# NMEA0183Breakout-2_0.net
KiCad netlist of a schematic drawn in EAGLE
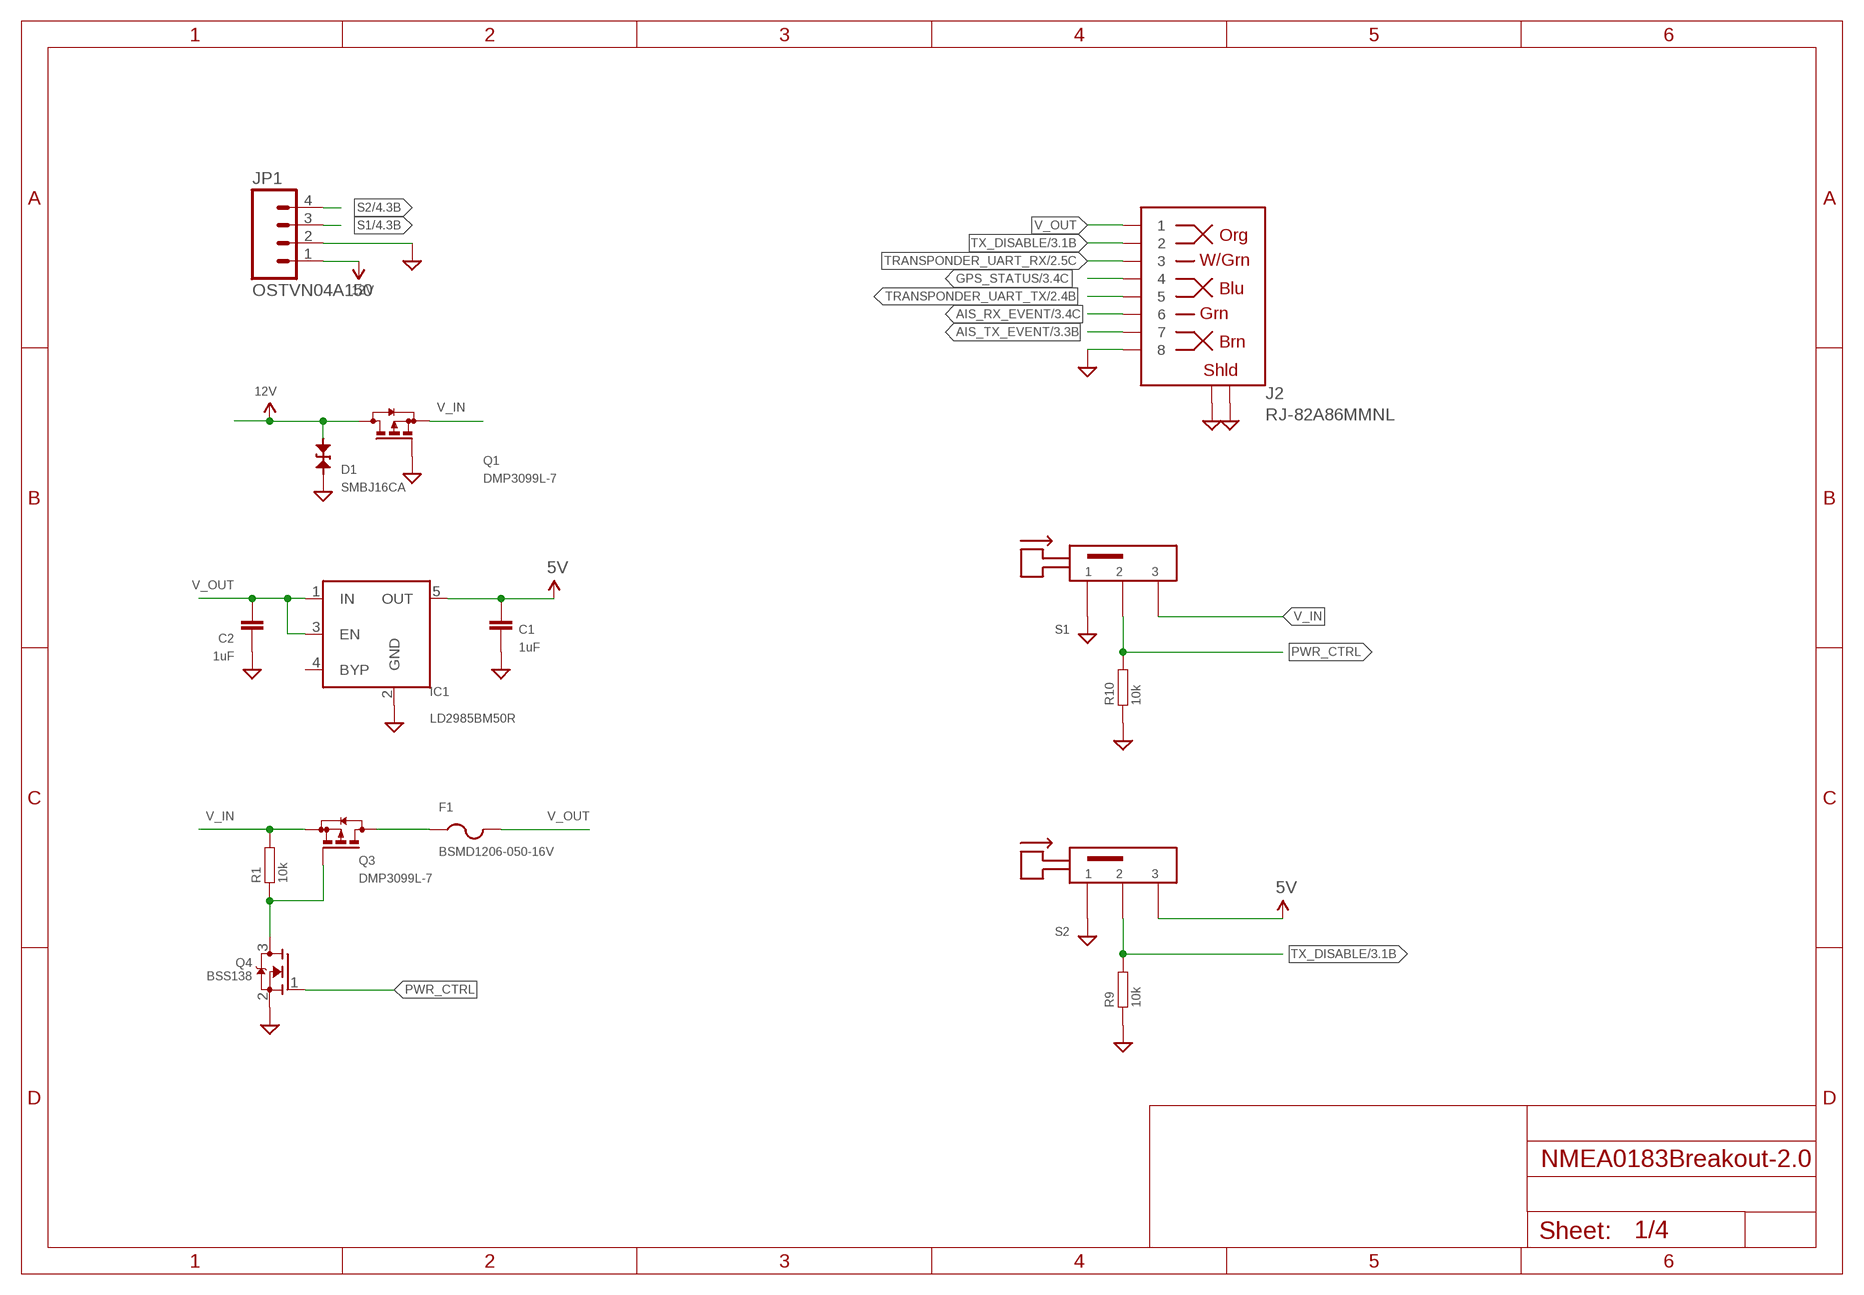
[diagram p0: schematic, sheet 1]
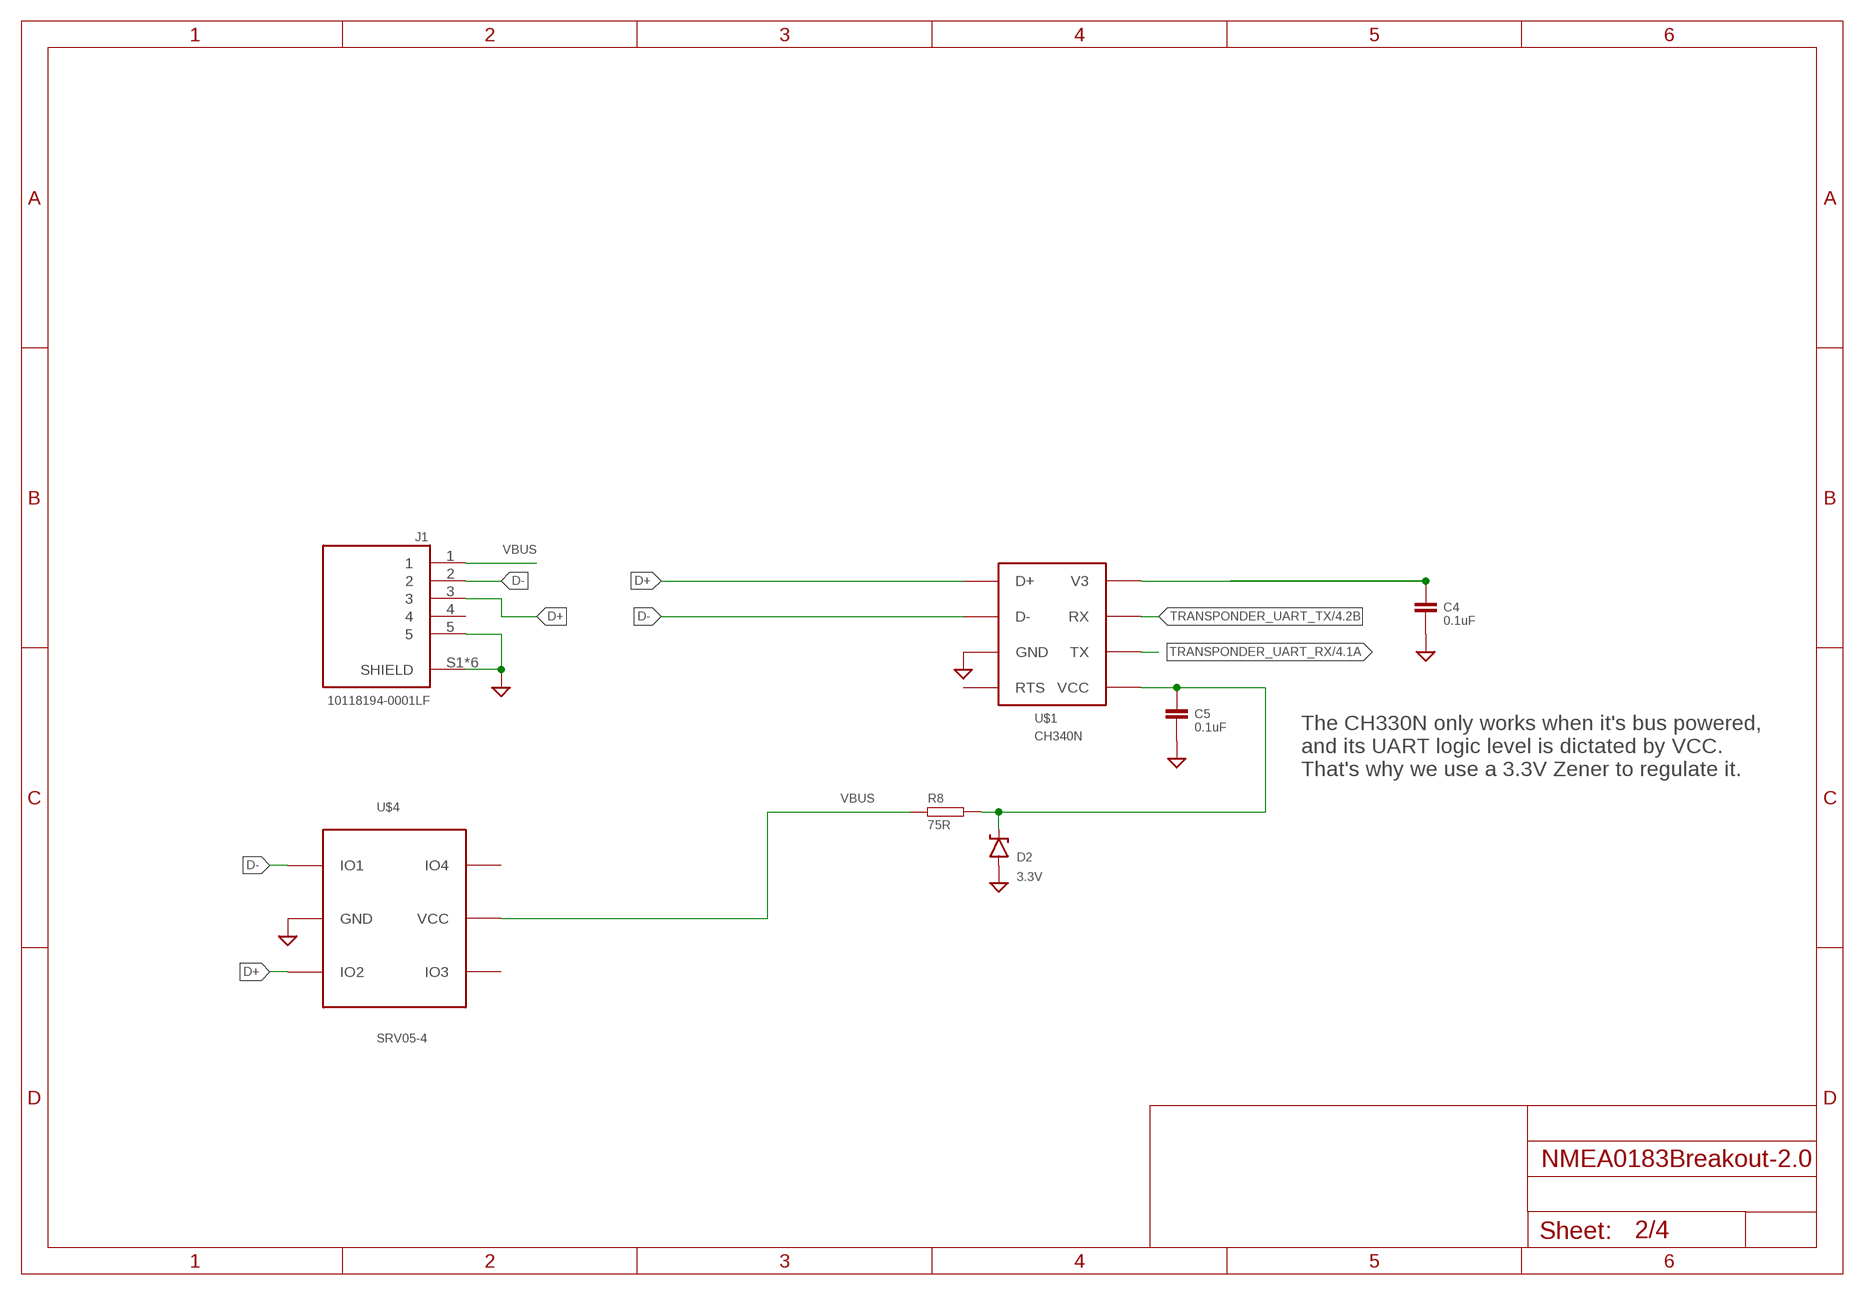
[diagram p1: schematic, sheet 2]
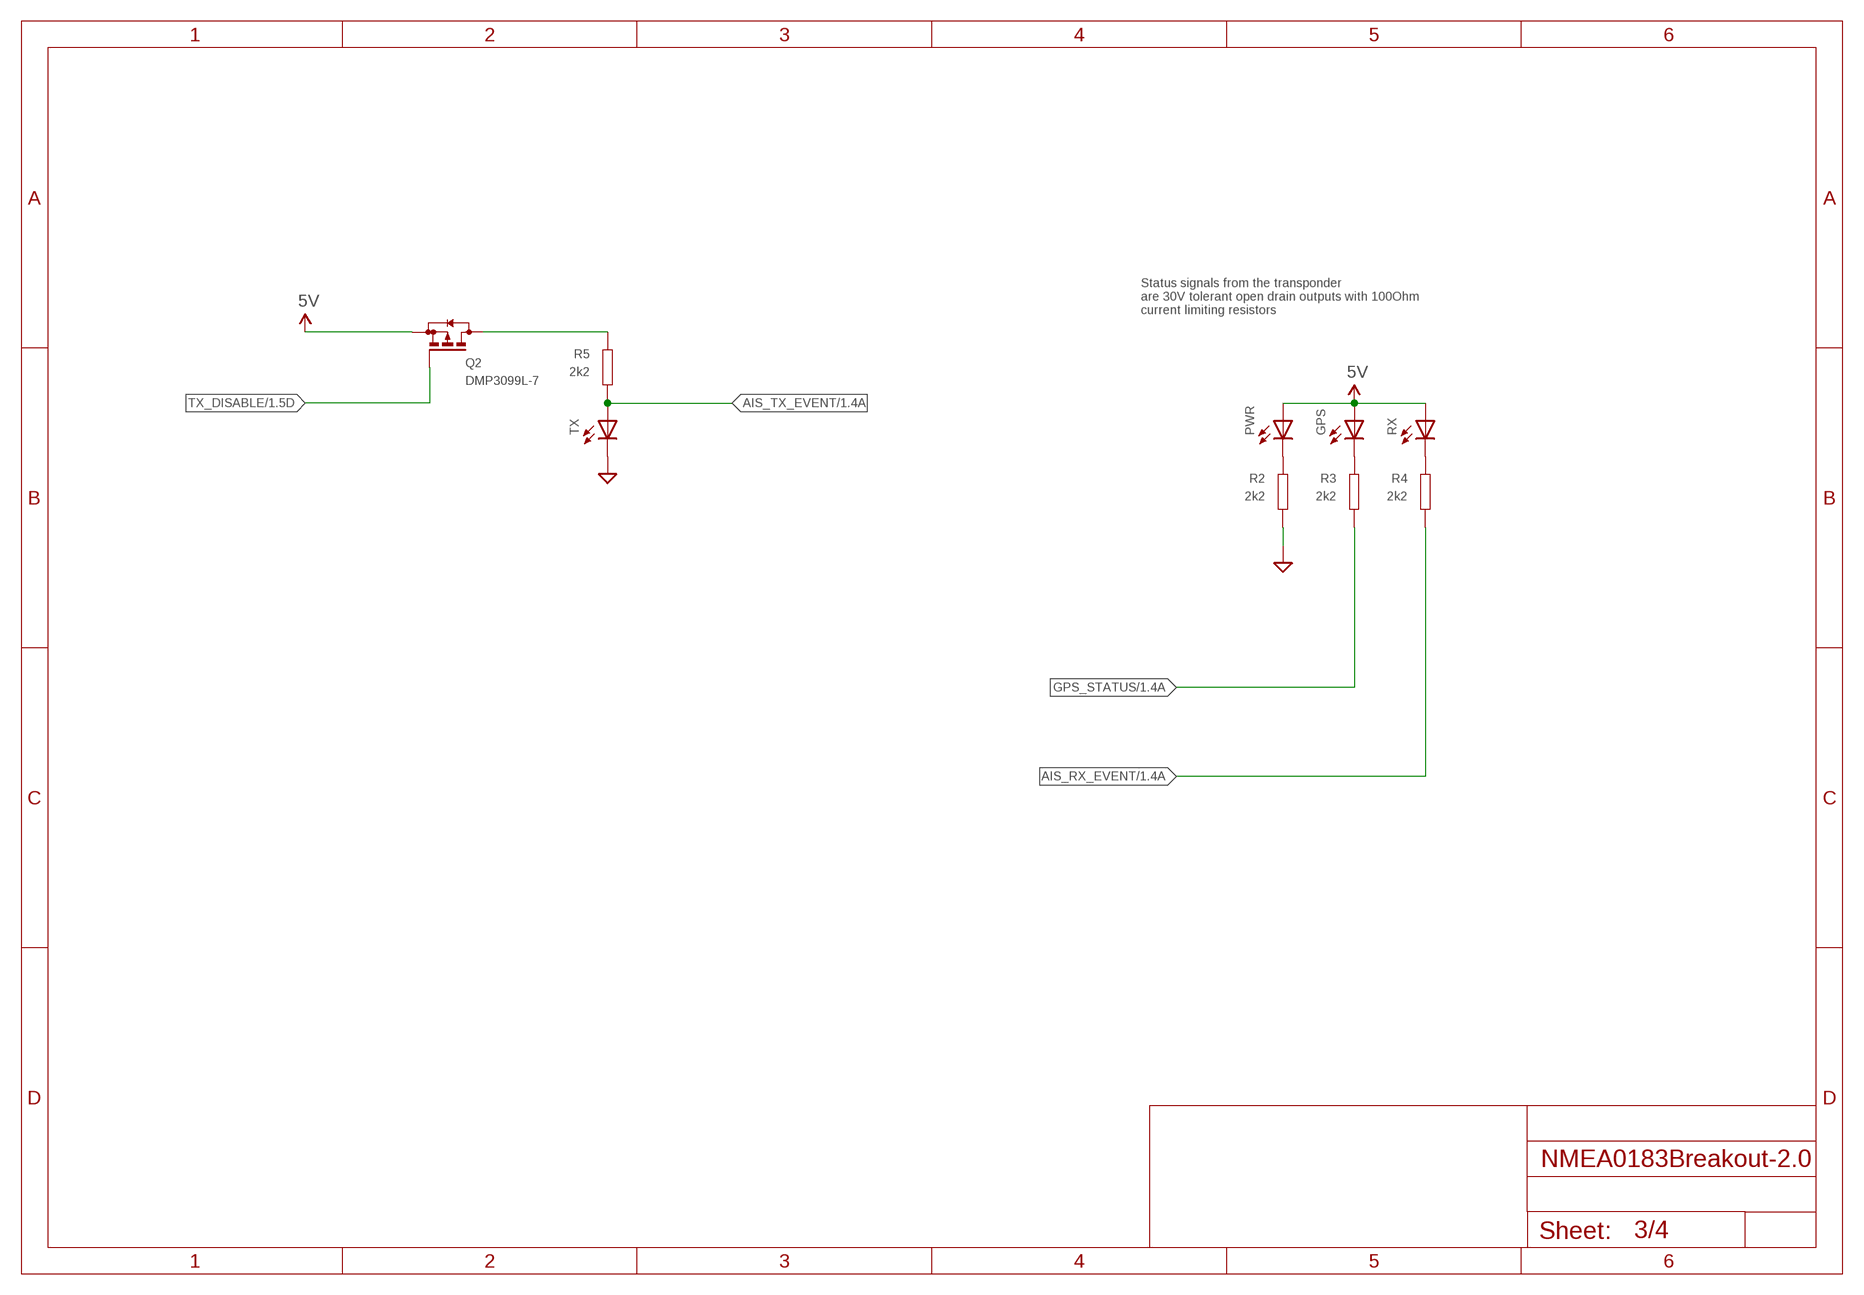
[diagram p2: schematic, sheet 3]
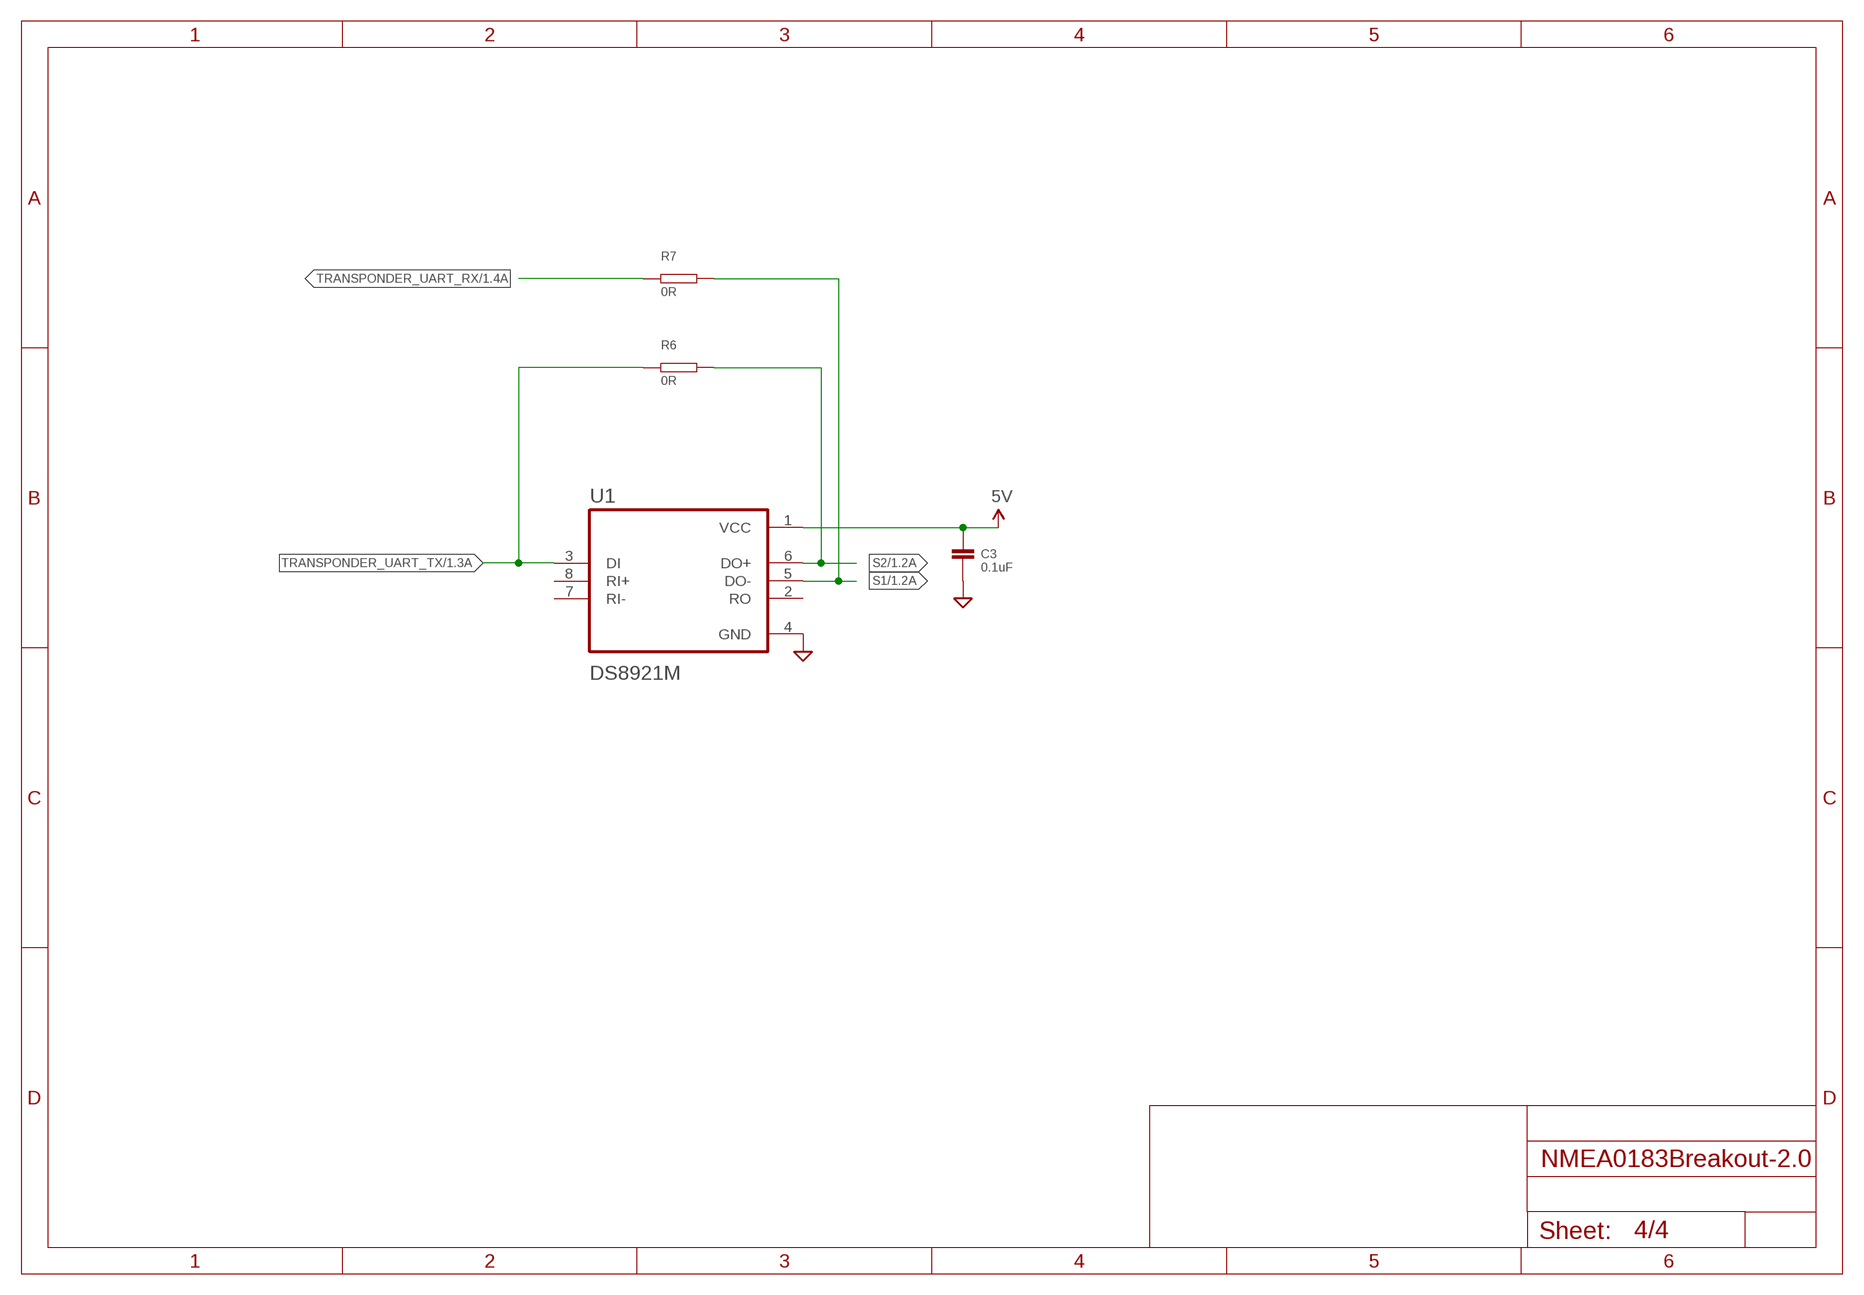
[diagram p3: schematic, sheet 4]

(export (version "E")
  (design (tool "Eeschema 10.0.6"))
  (components
    (comp (ref "C4")
      (value "0.1uF")
      (footprint "eagle-import:0603")
      (libsource (lib "eagle-import") (part "CAPACITOR0603"))
    )
    (comp (ref "C5")
      (value "0.1uF")
      (footprint "eagle-import:0603")
      (libsource (lib "eagle-import") (part "CAPACITOR0603"))
    )
    (comp (ref "D2")
      (value "3.3V")
      (footprint "eagle-import:SOD-323")
      (libsource (lib "eagle-import") (part "DIODE-ZENER3.3V"))
    )
    (comp (ref "J1")
      (value "10118194-0001LF")
      (footprint "eagle-import:AMPHENOL_10118194-0001LF")
      (fields (field (name "MF") "Amphenol ICC (FCI)"))
      (libsource (lib "eagle-import") (part "10118194-0001LF"))
    )
    (comp (ref "R8")
      (value "75R")
      (footprint "eagle-import:0603")
      (libsource (lib "eagle-import") (part "RESISTOR0603"))
    )
    (comp (ref "U$1")
      (value "CH340N")
      (footprint "eagle-import:SOIC-8")
      (libsource (lib "eagle-import") (part "CH330N"))
    )
    (comp (ref "U$4")
      (value "SRV05-4")
      (footprint "eagle-import:SOT23-6")
      (libsource (lib "eagle-import") (part "SRV05-4"))
    )
    (comp (ref "C3")
      (value "0.1uF")
      (footprint "eagle-import:0603")
      (libsource (lib "eagle-import") (part "CAPACITOR0603"))
    )
    (comp (ref "R6")
      (value "0R")
      (footprint "eagle-import:0603")
      (libsource (lib "eagle-import") (part "RESISTOR0603"))
    )
    (comp (ref "R7")
      (value "0R")
      (footprint "eagle-import:0603")
      (libsource (lib "eagle-import") (part "RESISTOR0603"))
    )
    (comp (ref "U1")
      (value "DS8921M")
      (footprint "eagle-import:SOIC127P599X175-8N")
      (fields (field (name "MF") "Texas Instruments") (field (name "MP") "DS8921M/NOPB"))
      (libsource (lib "eagle-import") (part "DS8921M"))
    )
    (comp (ref "C1")
      (value "1uF")
      (footprint "eagle-import:0603")
      (libsource (lib "eagle-import") (part "CAPACITOR0603"))
    )
    (comp (ref "C2")
      (value "1uF")
      (footprint "eagle-import:0603")
      (libsource (lib "eagle-import") (part "CAPACITOR0603"))
    )
    (comp (ref "D1")
      (value "SMBJ16CA")
      (footprint "eagle-import:SMB-BIDIR")
      (libsource (lib "eagle-import") (part "DIODE-TVS-BIDIRSMB"))
    )
    (comp (ref "F1")
      (value "BSMD1206-050-16V")
      (footprint "eagle-import:R1206")
      (libsource (lib "eagle-import") (part "PTCFUSE-1206"))
    )
    (comp (ref "IC1")
      (value "LD2985BM50R")
      (footprint "eagle-import:SOT23-5")
      (libsource (lib "eagle-import") (part "MIC5219XX"))
    )
    (comp (ref "J2")
      (value "RJ-82A86MMNL")
      (footprint "eagle-import:RJ-82A86MMNL")
      (libsource (lib "eagle-import") (part "RJ-82A86MMNL"))
    )
    (comp (ref "JP1")
      (value "OSTVN04A150")
      (footprint "eagle-import:1X04")
      (libsource (lib "eagle-import") (part "M04PTH"))
    )
    (comp (ref "Q1")
      (value "DMP3099L-7")
      (footprint "eagle-import:SOT23")
      (libsource (lib "eagle-import") (part "BSS84"))
    )
    (comp (ref "Q3")
      (value "DMP3099L-7")
      (footprint "eagle-import:SOT23")
      (libsource (lib "eagle-import") (part "BSS84"))
    )
    (comp (ref "Q4")
      (value "BSS138")
      (footprint "eagle-import:SOT23")
      (libsource (lib "eagle-import") (part "MOSFET-NREFLOW"))
    )
    (comp (ref "R1")
      (value "10k")
      (footprint "eagle-import:0603")
      (libsource (lib "eagle-import") (part "RESISTOR0603"))
    )
    (comp (ref "R9")
      (value "10k")
      (footprint "eagle-import:0603")
      (libsource (lib "eagle-import") (part "RESISTOR0603"))
    )
    (comp (ref "R10")
      (value "10k")
      (footprint "eagle-import:0603")
      (libsource (lib "eagle-import") (part "RESISTOR0603"))
    )
    (comp (ref "S1")
      (value "LC1258XXNP")
      (footprint "eagle-import:LC1258XXNP")
      (libsource (lib "eagle-import") (part "LC1258XXNP"))
    )
    (comp (ref "S2")
      (value "LC1258XXNP")
      (footprint "eagle-import:LC1258XXNP")
      (libsource (lib "eagle-import") (part "LC1258XXNP"))
    )
    (comp (ref "GPS")
      (value "LEDCHIPLED_1206")
      (footprint "eagle-import:CHIPLED_1206")
      (fields (field (name "PARTNO") "TJ-S3216CL9T5ALC2G-A5"))
      (libsource (lib "eagle-import") (part "LEDCHIPLED_1206"))
    )
    (comp (ref "PWR")
      (value "LEDCHIPLED_1206")
      (footprint "eagle-import:CHIPLED_1206")
      (fields (field (name "PARTNO") "TJ-S3216CL9T5ALC2G-A5"))
      (libsource (lib "eagle-import") (part "LEDCHIPLED_1206"))
    )
    (comp (ref "Q2")
      (value "DMP3099L-7")
      (footprint "eagle-import:SOT23")
      (libsource (lib "eagle-import") (part "BSS84"))
    )
    (comp (ref "R2")
      (value "2k2")
      (footprint "eagle-import:0603")
      (libsource (lib "eagle-import") (part "RESISTOR0603"))
    )
    (comp (ref "R3")
      (value "2k2")
      (footprint "eagle-import:0603")
      (libsource (lib "eagle-import") (part "RESISTOR0603"))
    )
    (comp (ref "R4")
      (value "2k2")
      (footprint "eagle-import:0603")
      (libsource (lib "eagle-import") (part "RESISTOR0603"))
    )
    (comp (ref "R5")
      (value "2k2")
      (footprint "eagle-import:0603")
      (libsource (lib "eagle-import") (part "RESISTOR0603"))
    )
    (comp (ref "RX")
      (value "LEDCHIPLED_1206")
      (footprint "eagle-import:CHIPLED_1206")
      (fields (field (name "PARTNO") "TJ-S3216CL9T5ALC2G-A5"))
      (libsource (lib "eagle-import") (part "LEDCHIPLED_1206"))
    )
    (comp (ref "TX")
      (value "LEDCHIPLED_1206")
      (footprint "eagle-import:CHIPLED_1206")
      (fields (field (name "PARTNO") "TJ-S3216CL9T5ALC2G-A5"))
      (libsource (lib "eagle-import") (part "LEDCHIPLED_1206"))
    )
  )
  (nets
    (net (code "1") (name "5V") (class "Default")
      (node (ref "C1") (pin "P$1") (pinfunction "1_P$1") (pintype "passive"))
      (node (ref "C3") (pin "P$1") (pinfunction "1_P$1") (pintype "passive"))
      (node (ref "GPS") (pin "A") (pinfunction "A_A") (pintype "passive"))
      (node (ref "IC1") (pin "5") (pinfunction "OUT_5") (pintype "output"))
      (node (ref "PWR") (pin "A") (pinfunction "A_A") (pintype "passive"))
      (node (ref "Q2") (pin "2") (pinfunction "S_2") (pintype "passive"))
      (node (ref "RX") (pin "A") (pinfunction "A_A") (pintype "passive"))
      (node (ref "S2") (pin "P$3") (pinfunction "3_P$3") (pintype "bidirectional"))
      (node (ref "U1") (pin "1") (pinfunction "VCC_1") (pintype "power_in"))
    )
    (net (code "2") (name "12V") (class "Default")
      (node (ref "D1") (pin "A") (pinfunction "P$1_A") (pintype "bidirectional"))
      (node (ref "JP1") (pin "1") (pinfunction "1_1") (pintype "passive"))
      (node (ref "Q1") (pin "3") (pinfunction "D_3") (pintype "passive"))
    )
    (net (code "3") (name "AIS_RX_EVENT") (class "Default")
      (node (ref "J2") (pin "P$6") (pinfunction "6_P$6") (pintype "bidirectional"))
      (node (ref "R4") (pin "P$2") (pinfunction "P$2_P$2") (pintype "passive"))
    )
    (net (code "4") (name "AIS_TX_EVENT") (class "Default")
      (node (ref "J2") (pin "P$7") (pinfunction "7_P$7") (pintype "bidirectional"))
      (node (ref "R5") (pin "P$2") (pinfunction "P$2_P$2") (pintype "passive"))
      (node (ref "TX") (pin "A") (pinfunction "A_A") (pintype "passive"))
    )
    (net (code "5") (name "D+") (class "Default")
      (node (ref "J1") (pin "3") (pinfunction "3_3") (pintype "passive"))
      (node (ref "U$1") (pin "1") (pinfunction "D+_1") (pintype "bidirectional"))
      (node (ref "U$4") (pin "3") (pinfunction "IO2_3") (pintype "bidirectional"))
    )
    (net (code "6") (name "D-") (class "Default")
      (node (ref "J1") (pin "2") (pinfunction "2_2") (pintype "passive"))
      (node (ref "U$1") (pin "2") (pinfunction "D-_2") (pintype "bidirectional"))
      (node (ref "U$4") (pin "1") (pinfunction "IO1_1") (pintype "bidirectional"))
    )
    (net (code "7") (name "GND") (class "Default")
      (node (ref "C1") (pin "P$2") (pinfunction "2_P$2") (pintype "passive"))
      (node (ref "C2") (pin "P$2") (pinfunction "2_P$2") (pintype "passive"))
      (node (ref "C3") (pin "P$2") (pinfunction "2_P$2") (pintype "passive"))
      (node (ref "C4") (pin "P$2") (pinfunction "2_P$2") (pintype "passive"))
      (node (ref "C5") (pin "P$2") (pinfunction "2_P$2") (pintype "passive"))
      (node (ref "D1") (pin "C") (pinfunction "P$2_C") (pintype "bidirectional"))
      (node (ref "D2") (pin "A") (pinfunction "A_A") (pintype "passive"))
      (node (ref "IC1") (pin "2") (pinfunction "GND_2") (pintype "power_in"))
      (node (ref "J1") (pin "5") (pinfunction "5_5") (pintype "passive"))
      (node (ref "J1") (pin "S1") (pinfunction "SHIELD_S1") (pintype "passive"))
      (node (ref "J1") (pin "S2") (pinfunction "SHIELD_S2") (pintype "passive"))
      (node (ref "J1") (pin "S3") (pinfunction "SHIELD_S3") (pintype "passive"))
      (node (ref "J1") (pin "S4") (pinfunction "SHIELD_S4") (pintype "passive"))
      (node (ref "J1") (pin "S5") (pinfunction "SHIELD_S5") (pintype "passive"))
      (node (ref "J1") (pin "S6") (pinfunction "SHIELD_S6") (pintype "passive"))
      (node (ref "J2") (pin "P$10") (pinfunction "SHLD_P$10") (pintype "bidirectional"))
      (node (ref "J2") (pin "P$11") (pinfunction "SHLD_P$11") (pintype "bidirectional"))
      (node (ref "J2") (pin "P$12") (pinfunction "SHLD_P$12") (pintype "bidirectional"))
      (node (ref "J2") (pin "P$8") (pinfunction "8_P$8") (pintype "bidirectional"))
      (node (ref "J2") (pin "P$9") (pinfunction "SHLD_P$9") (pintype "bidirectional"))
      (node (ref "JP1") (pin "2") (pinfunction "2_2") (pintype "passive"))
      (node (ref "Q1") (pin "1") (pinfunction "G_1") (pintype "passive"))
      (node (ref "Q4") (pin "2") (pinfunction "S_2") (pintype "bidirectional"))
      (node (ref "R10") (pin "P$1") (pinfunction "P$1_P$1") (pintype "passive"))
      (node (ref "R2") (pin "P$2") (pinfunction "P$2_P$2") (pintype "passive"))
      (node (ref "R9") (pin "P$1") (pinfunction "P$1_P$1") (pintype "passive"))
      (node (ref "S1") (pin "P$1") (pinfunction "1_P$1") (pintype "bidirectional"))
      (node (ref "S2") (pin "P$1") (pinfunction "1_P$1") (pintype "bidirectional"))
      (node (ref "TX") (pin "C") (pinfunction "C_C") (pintype "passive"))
      (node (ref "U$1") (pin "3") (pinfunction "GND_3") (pintype "bidirectional"))
      (node (ref "U$4") (pin "2") (pinfunction "GND_2") (pintype "bidirectional"))
      (node (ref "U1") (pin "4") (pinfunction "GND_4") (pintype "power_in"))
    )
    (net (code "8") (name "GPS_STATUS") (class "Default")
      (node (ref "J2") (pin "P$4") (pinfunction "4_P$4") (pintype "bidirectional"))
      (node (ref "R3") (pin "P$2") (pinfunction "P$2_P$2") (pintype "passive"))
    )
    (net (code "9") (name "Net-(C4-1)") (class "Default")
      (node (ref "C4") (pin "P$1") (pinfunction "1_P$1") (pintype "passive"))
      (node (ref "U$1") (pin "8") (pinfunction "V3_8") (pintype "bidirectional"))
    )
    (net (code "10") (name "Net-(C5-1)") (class "Default")
      (node (ref "C5") (pin "P$1") (pinfunction "1_P$1") (pintype "passive"))
      (node (ref "D2") (pin "C") (pinfunction "C_C") (pintype "passive"))
      (node (ref "R8") (pin "P$2") (pinfunction "P$2_P$2") (pintype "passive"))
      (node (ref "U$1") (pin "5") (pinfunction "VCC_5") (pintype "bidirectional"))
    )
    (net (code "11") (name "Net-(GPS-PadC)") (class "Default")
      (node (ref "GPS") (pin "C") (pinfunction "C_C") (pintype "passive"))
      (node (ref "R3") (pin "P$1") (pinfunction "P$1_P$1") (pintype "passive"))
    )
    (net (code "12") (name "Net-(PWR-PadC)") (class "Default")
      (node (ref "PWR") (pin "C") (pinfunction "C_C") (pintype "passive"))
      (node (ref "R2") (pin "P$1") (pinfunction "P$1_P$1") (pintype "passive"))
    )
    (net (code "13") (name "Net-(Q2-D)") (class "Default")
      (node (ref "Q2") (pin "3") (pinfunction "D_3") (pintype "passive"))
      (node (ref "R5") (pin "P$1") (pinfunction "P$1_P$1") (pintype "passive"))
    )
    (net (code "14") (name "Net-(Q3-D)") (class "Default")
      (node (ref "F1") (pin "1") (pinfunction "1_1") (pintype "passive"))
      (node (ref "Q3") (pin "3") (pinfunction "D_3") (pintype "passive"))
    )
    (net (code "15") (name "Net-(Q3-G)") (class "Default")
      (node (ref "Q3") (pin "1") (pinfunction "G_1") (pintype "passive"))
      (node (ref "Q4") (pin "3") (pinfunction "D_3") (pintype "bidirectional"))
      (node (ref "R1") (pin "P$1") (pinfunction "P$1_P$1") (pintype "passive"))
    )
    (net (code "16") (name "Net-(R4-PadP$1)") (class "Default")
      (node (ref "R4") (pin "P$1") (pinfunction "P$1_P$1") (pintype "passive"))
      (node (ref "RX") (pin "C") (pinfunction "C_C") (pintype "passive"))
    )
    (net (code "17") (name "PWR_CTRL") (class "Default")
      (node (ref "Q4") (pin "1") (pinfunction "G_1") (pintype "bidirectional"))
      (node (ref "R10") (pin "P$2") (pinfunction "P$2_P$2") (pintype "passive"))
      (node (ref "S1") (pin "P$2") (pinfunction "2_P$2") (pintype "bidirectional"))
    )
    (net (code "18") (name "S1") (class "Default")
      (node (ref "JP1") (pin "3") (pinfunction "3_3") (pintype "passive"))
      (node (ref "R7") (pin "P$2") (pinfunction "P$2_P$2") (pintype "passive"))
      (node (ref "U1") (pin "5") (pinfunction "DO-_5") (pintype "output"))
    )
    (net (code "19") (name "S2") (class "Default")
      (node (ref "JP1") (pin "4") (pinfunction "4_4") (pintype "passive"))
      (node (ref "R6") (pin "P$2") (pinfunction "P$2_P$2") (pintype "passive"))
      (node (ref "U1") (pin "6") (pinfunction "DO+_6") (pintype "output"))
    )
    (net (code "20") (name "TRANSPONDER_UART_RX") (class "Default")
      (node (ref "J2") (pin "P$3") (pinfunction "3_P$3") (pintype "bidirectional"))
      (node (ref "R7") (pin "P$1") (pinfunction "P$1_P$1") (pintype "passive"))
      (node (ref "U$1") (pin "6") (pinfunction "TX_6") (pintype "bidirectional"))
    )
    (net (code "21") (name "TRANSPONDER_UART_TX") (class "Default")
      (node (ref "J2") (pin "P$5") (pinfunction "5_P$5") (pintype "bidirectional"))
      (node (ref "R6") (pin "P$1") (pinfunction "P$1_P$1") (pintype "passive"))
      (node (ref "U$1") (pin "7") (pinfunction "RX_7") (pintype "bidirectional"))
      (node (ref "U1") (pin "3") (pinfunction "DI_3") (pintype "input"))
    )
    (net (code "22") (name "TX_DISABLE") (class "Default")
      (node (ref "J2") (pin "P$2") (pinfunction "2_P$2") (pintype "bidirectional"))
      (node (ref "Q2") (pin "1") (pinfunction "G_1") (pintype "passive"))
      (node (ref "R9") (pin "P$2") (pinfunction "P$2_P$2") (pintype "passive"))
      (node (ref "S2") (pin "P$2") (pinfunction "2_P$2") (pintype "bidirectional"))
    )
    (net (code "23") (name "VBUS") (class "Default")
      (node (ref "J1") (pin "1") (pinfunction "1_1") (pintype "passive"))
      (node (ref "R8") (pin "P$1") (pinfunction "P$1_P$1") (pintype "passive"))
      (node (ref "U$4") (pin "5") (pinfunction "VCC_5") (pintype "bidirectional"))
    )
    (net (code "24") (name "V_IN") (class "Default")
      (node (ref "Q1") (pin "2") (pinfunction "S_2") (pintype "passive"))
      (node (ref "Q3") (pin "2") (pinfunction "S_2") (pintype "passive"))
      (node (ref "R1") (pin "P$2") (pinfunction "P$2_P$2") (pintype "passive"))
      (node (ref "S1") (pin "P$3") (pinfunction "3_P$3") (pintype "bidirectional"))
    )
    (net (code "25") (name "V_OUT") (class "Default")
      (node (ref "C2") (pin "P$1") (pinfunction "1_P$1") (pintype "passive"))
      (node (ref "F1") (pin "2") (pinfunction "2_2") (pintype "passive"))
      (node (ref "IC1") (pin "1") (pinfunction "IN_1") (pintype "input"))
      (node (ref "IC1") (pin "3") (pinfunction "EN_3") (pintype "input"))
      (node (ref "J2") (pin "P$1") (pinfunction "1_P$1") (pintype "bidirectional"))
    )
    (net (code "26") (name "unconnected-(IC1-BYP-Pad4)") (class "Default")
      (node (ref "IC1") (pin "4") (pinfunction "BYP_4") (pintype "passive"))
    )
    (net (code "27") (name "unconnected-(J1-Pad4)") (class "Default")
      (node (ref "J1") (pin "4") (pinfunction "4_4") (pintype "passive"))
    )
    (net (code "28") (name "unconnected-(U$1-RTS-Pad4)") (class "Default")
      (node (ref "U$1") (pin "4") (pinfunction "RTS_4") (pintype "bidirectional"))
    )
    (net (code "29") (name "unconnected-(U$4-IO3-Pad4)") (class "Default")
      (node (ref "U$4") (pin "4") (pinfunction "IO3_4") (pintype "bidirectional"))
    )
    (net (code "30") (name "unconnected-(U$4-IO4-Pad6)") (class "Default")
      (node (ref "U$4") (pin "6") (pinfunction "IO4_6") (pintype "bidirectional"))
    )
    (net (code "31") (name "unconnected-(U1-RI+-Pad8)") (class "Default")
      (node (ref "U1") (pin "8") (pinfunction "RI+_8") (pintype "input"))
    )
    (net (code "32") (name "unconnected-(U1-RI--Pad7)") (class "Default")
      (node (ref "U1") (pin "7") (pinfunction "RI-_7") (pintype "input"))
    )
    (net (code "33") (name "unconnected-(U1-RO-Pad2)") (class "Default")
      (node (ref "U1") (pin "2") (pinfunction "RO_2") (pintype "output"))
    )
  )
)
